# 2_ADSTM32-MCU.net
KiCad netlist of a schematic drawn in Altium Designer
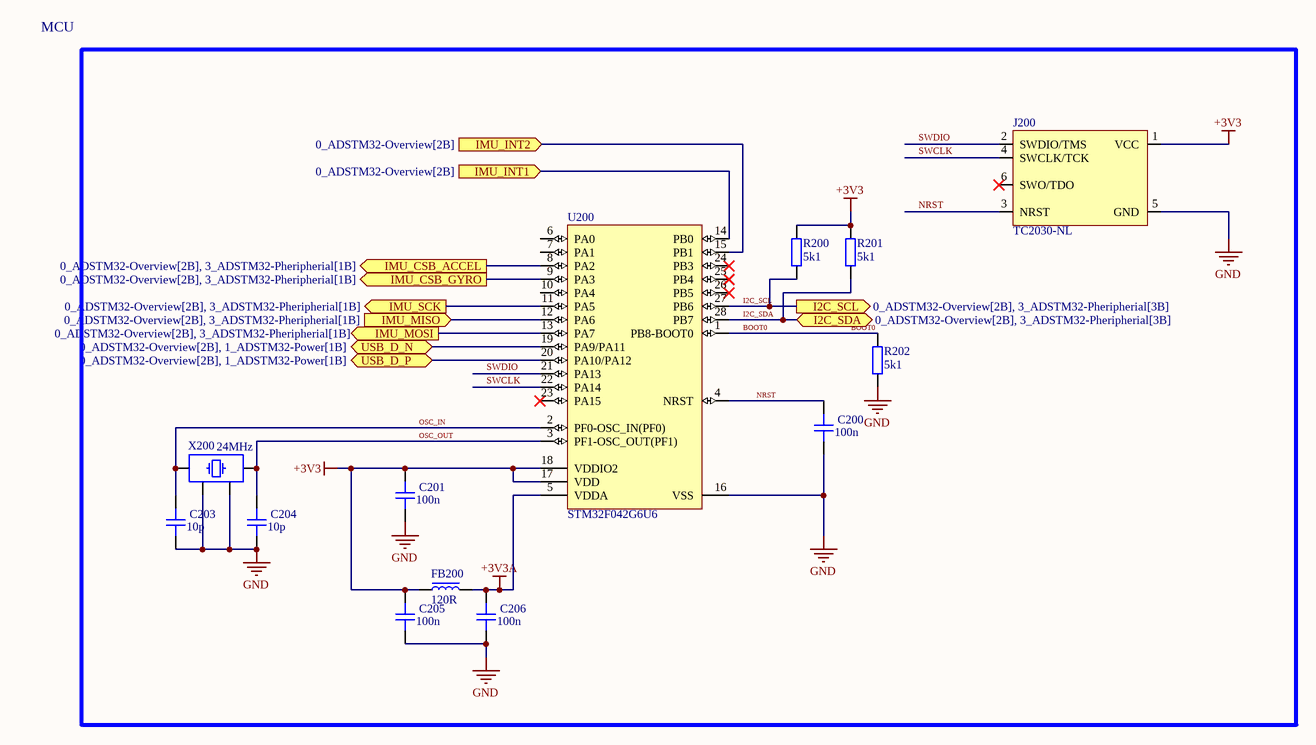
[diagram p0: 2_ADSTM32-MCU.SchDoc]

(export (version "E")
  (design (tool "Eeschema 10.0.6"))
  (components
    (comp (ref "C200")
      (value "100n")
      (footprint "CAP_0603")
      (description "Capacitor SMD 0603 16V")
      (libsource (lib "Schematic-Lib-PhilsLab") (part "CAP_0603_16V"))
    )
    (comp (ref "C201")
      (value "100n")
      (footprint "CAP_0603")
      (description "Capacitor SMD 0603 16V")
      (libsource (lib "Schematic-Lib-PhilsLab") (part "CAP_0603_16V"))
    )
    (comp (ref "C203")
      (value "10p")
      (footprint "CAP_0603")
      (description "Capacitor SMD 0603 16V")
      (libsource (lib "Schematic-Lib-PhilsLab") (part "CAP_0603_16V"))
    )
    (comp (ref "C204")
      (value "10p")
      (footprint "CAP_0603")
      (description "Capacitor SMD 0603 16V")
      (libsource (lib "Schematic-Lib-PhilsLab") (part "CAP_0603_16V"))
    )
    (comp (ref "C205")
      (value "100n")
      (footprint "CAP_0603")
      (description "Capacitor SMD 0603 16V")
      (libsource (lib "Schematic-Lib-PhilsLab") (part "CAP_0603_16V"))
    )
    (comp (ref "C206")
      (value "100n")
      (footprint "CAP_0603")
      (description "Capacitor SMD 0603 16V")
      (libsource (lib "Schematic-Lib-PhilsLab") (part "CAP_0603_16V"))
    )
    (comp (ref "FB200")
      (value "120R")
      (footprint "FB_0603")
      (description "Ferrite Bead SMD 0603")
      (libsource (lib "Schematic-Lib-PhilsLab") (part "FB_0603"))
    )
    (comp (ref "J200")
      (value "TC2030-NL")
      (footprint "TC2030-NL-FP")
      (description "Tag-Connect No-Solder SWD Debug Connector (No Legs) DO NOT PLACE")
      (fields
        (field (name "MANUFACTURER") "Tag-Connect")
        (field (name "MANUFACTURER PART NUMBER") "TC2030-NL-FP")
      )
      (libsource (lib "Schematic-Lib-PhilsLab") (part "TC2030-NL"))
    )
    (comp (ref "R200")
      (value "5k1")
      (footprint "RES_0603")
      (description "Resistor SMD 0603")
      (libsource (lib "Schematic-Lib-PhilsLab") (part "RES_0603"))
    )
    (comp (ref "R201")
      (value "5k1")
      (footprint "RES_0603")
      (description "Resistor SMD 0603")
      (libsource (lib "Schematic-Lib-PhilsLab") (part "RES_0603"))
    )
    (comp (ref "R202")
      (value "5k1")
      (footprint "RES_0603")
      (description "Resistor SMD 0603")
      (libsource (lib "Schematic-Lib-PhilsLab") (part "RES_0603"))
    )
    (comp (ref "U200")
      (value "STM32F042G6U6")
      (footprint "STM-UFQFPN28_V")
      (fields (field (name "MANUFACTURER") "STMicroelectronics"))
      (libsource (lib "Altium Content Vault") (part "MC-ARM-STM32F042-UFQFPN28"))
    )
    (comp (ref "X200")
      (value "24MHz")
      (footprint "XTAL_3225")
      (description "Crystal SMD 24MHz 10PPM 7pF 3225")
      (fields (field (name "MANUFACTURER") "Epson"))
      (libsource (lib "Schematic-Lib-PhilsLab") (part "TSX-3225_24.0000MF15X-AC"))
    )
  )
  (nets
    (net (code "1") (name "+3V3") (class "Default")
      (node (ref "C201") (pin "2") (pinfunction "2_2") (pintype "passive"))
      (node (ref "C205") (pin "2") (pinfunction "2_2") (pintype "passive"))
      (node (ref "FB200") (pin "1") (pinfunction "1_1") (pintype "passive"))
      (node (ref "J200") (pin "1") (pinfunction "VCC_1") (pintype "passive"))
      (node (ref "R200") (pin "2") (pinfunction "2_2") (pintype "passive"))
      (node (ref "R201") (pin "2") (pinfunction "2_2") (pintype "passive"))
      (node (ref "U200") (pin "17") (pinfunction "VDD_17") (pintype "power_in"))
      (node (ref "U200") (pin "18") (pinfunction "VDDIO2_18") (pintype "power_in"))
    )
    (net (code "2") (name "+3V3A") (class "Default")
      (node (ref "C206") (pin "2") (pinfunction "2_2") (pintype "passive"))
      (node (ref "FB200") (pin "2") (pinfunction "2_2") (pintype "passive"))
      (node (ref "U200") (pin "5") (pinfunction "VDDA_5") (pintype "power_in"))
    )
    (net (code "3") (name "/BOOT0") (class "Default")
      (node (ref "R202") (pin "2") (pinfunction "2_2") (pintype "passive"))
      (node (ref "U200") (pin "1") (pinfunction "PB8-BOOT0_1") (pintype "bidirectional"))
    )
    (net (code "4") (name "/I2C_SCL") (class "Default")
      (node (ref "R200") (pin "1") (pinfunction "1_1") (pintype "passive"))
      (node (ref "U200") (pin "27") (pinfunction "PB6_27") (pintype "bidirectional"))
    )
    (net (code "5") (name "/I2C_SDA") (class "Default")
      (node (ref "R201") (pin "1") (pinfunction "1_1") (pintype "passive"))
      (node (ref "U200") (pin "28") (pinfunction "PB7_28") (pintype "bidirectional"))
    )
    (net (code "6") (name "/IMU_CSB_ACCEL") (class "Default")
      (node (ref "U200") (pin "8") (pinfunction "PA2_8") (pintype "bidirectional"))
    )
    (net (code "7") (name "/IMU_CSB_GYRO") (class "Default")
      (node (ref "U200") (pin "9") (pinfunction "PA3_9") (pintype "bidirectional"))
    )
    (net (code "8") (name "/IMU_INT1") (class "Default")
      (node (ref "U200") (pin "14") (pinfunction "PB0_14") (pintype "bidirectional"))
    )
    (net (code "9") (name "/IMU_INT2") (class "Default")
      (node (ref "U200") (pin "15") (pinfunction "PB1_15") (pintype "bidirectional"))
    )
    (net (code "10") (name "/IMU_MISO") (class "Default")
      (node (ref "U200") (pin "12") (pinfunction "PA6_12") (pintype "bidirectional"))
    )
    (net (code "11") (name "/IMU_MOSI") (class "Default")
      (node (ref "U200") (pin "13") (pinfunction "PA7_13") (pintype "bidirectional"))
    )
    (net (code "12") (name "/IMU_SCK") (class "Default")
      (node (ref "U200") (pin "11") (pinfunction "PA5_11") (pintype "bidirectional"))
    )
    (net (code "13") (name "/NRST") (class "Default")
      (node (ref "C200") (pin "2") (pinfunction "2_2") (pintype "passive"))
      (node (ref "J200") (pin "3") (pinfunction "NRST_3") (pintype "passive"))
      (node (ref "U200") (pin "4") (pinfunction "NRST_4") (pintype "bidirectional"))
    )
    (net (code "14") (name "/OSC_IN") (class "Default")
      (node (ref "C203") (pin "2") (pinfunction "2_2") (pintype "passive"))
      (node (ref "U200") (pin "2") (pinfunction "PF0-OSC_IN(PF0)_2") (pintype "bidirectional"))
      (node (ref "X200") (pin "1") (pinfunction "1_1") (pintype "passive"))
    )
    (net (code "15") (name "/OSC_OUT") (class "Default")
      (node (ref "C204") (pin "2") (pinfunction "2_2") (pintype "passive"))
      (node (ref "U200") (pin "3") (pinfunction "PF1-OSC_OUT(PF1)_3") (pintype "bidirectional"))
      (node (ref "X200") (pin "3") (pinfunction "3_3") (pintype "passive"))
    )
    (net (code "16") (name "/SWCLK") (class "Default")
      (node (ref "J200") (pin "4") (pinfunction "SWCLK/TCK_4") (pintype "passive"))
      (node (ref "U200") (pin "22") (pinfunction "PA14_22") (pintype "bidirectional"))
    )
    (net (code "17") (name "/SWDIO") (class "Default")
      (node (ref "J200") (pin "2") (pinfunction "SWDIO/TMS_2") (pintype "passive"))
      (node (ref "U200") (pin "21") (pinfunction "PA13_21") (pintype "bidirectional"))
    )
    (net (code "18") (name "/USB_D_N") (class "Default")
      (node (ref "U200") (pin "19") (pinfunction "PA9/PA11_19") (pintype "bidirectional"))
    )
    (net (code "19") (name "/USB_D_P") (class "Default")
      (node (ref "U200") (pin "20") (pinfunction "PA10/PA12_20") (pintype "bidirectional"))
    )
    (net (code "20") (name "GND") (class "Default")
      (node (ref "C200") (pin "1") (pinfunction "1_1") (pintype "passive"))
      (node (ref "C201") (pin "1") (pinfunction "1_1") (pintype "passive"))
      (node (ref "C203") (pin "1") (pinfunction "1_1") (pintype "passive"))
      (node (ref "C204") (pin "1") (pinfunction "1_1") (pintype "passive"))
      (node (ref "C205") (pin "1") (pinfunction "1_1") (pintype "passive"))
      (node (ref "C206") (pin "1") (pinfunction "1_1") (pintype "passive"))
      (node (ref "J200") (pin "5") (pinfunction "GND_5") (pintype "passive"))
      (node (ref "R202") (pin "1") (pinfunction "1_1") (pintype "passive"))
      (node (ref "U200") (pin "16") (pinfunction "VSS_16") (pintype "power_in"))
      (node (ref "X200") (pin "2") (pinfunction "2_2") (pintype "passive"))
      (node (ref "X200") (pin "4") (pinfunction "4_4") (pintype "passive"))
    )
    (net (code "21") (name "unconnected-(J200-SWO{slash}TDO-Pad6)") (class "Default")
      (node (ref "J200") (pin "6") (pinfunction "SWO/TDO_6") (pintype "passive+no_connect"))
    )
    (net (code "22") (name "unconnected-(U200-PA0-Pad6)") (class "Default")
      (node (ref "U200") (pin "6") (pinfunction "PA0_6") (pintype "bidirectional"))
    )
    (net (code "23") (name "unconnected-(U200-PA1-Pad7)") (class "Default")
      (node (ref "U200") (pin "7") (pinfunction "PA1_7") (pintype "bidirectional"))
    )
    (net (code "24") (name "unconnected-(U200-PA4-Pad10)") (class "Default")
      (node (ref "U200") (pin "10") (pinfunction "PA4_10") (pintype "bidirectional"))
    )
    (net (code "25") (name "unconnected-(U200-PA15-Pad23)") (class "Default")
      (node (ref "U200") (pin "23") (pinfunction "PA15_23") (pintype "bidirectional+no_connect"))
    )
    (net (code "26") (name "unconnected-(U200-PB3-Pad24)") (class "Default")
      (node (ref "U200") (pin "24") (pinfunction "PB3_24") (pintype "bidirectional+no_connect"))
    )
    (net (code "27") (name "unconnected-(U200-PB4-Pad25)") (class "Default")
      (node (ref "U200") (pin "25") (pinfunction "PB4_25") (pintype "bidirectional+no_connect"))
    )
    (net (code "28") (name "unconnected-(U200-PB5-Pad26)") (class "Default")
      (node (ref "U200") (pin "26") (pinfunction "PB5_26") (pintype "bidirectional+no_connect"))
    )
  )
)
